# 11_Speak.net
KiCad netlist of a schematic drawn in Altium Designer
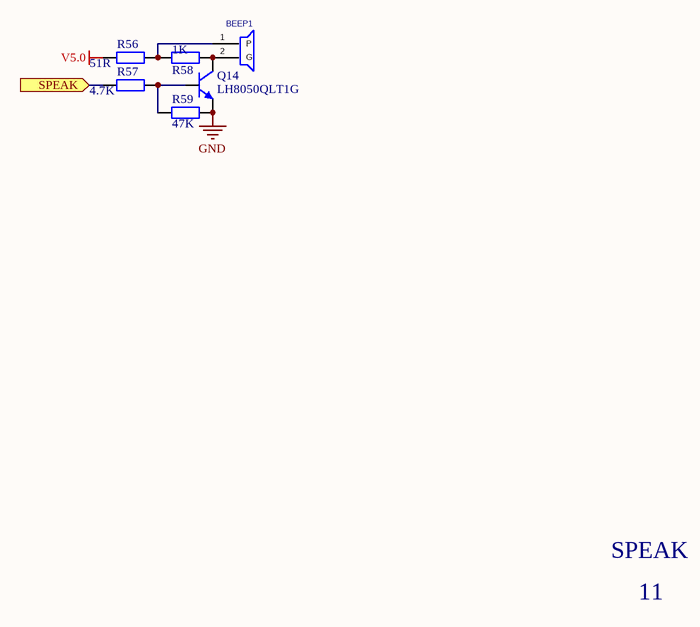
[diagram p0: 11_Speak.SchDoc]

(export (version "E")
  (design (tool "Eeschema 10.0.6"))
  (components
    (comp (ref "BEEP1")
      (value "BEEP-9.5X5.5")
      (footprint "BEEP-9.5X5.5")
      (libsource (lib "MINI-V3") (part "BEEP-9.5X5.5"))
    )
    (comp (ref "Q14")
      (value "LH8050QLT1G")
      (footprint "SOT-23")
      (description "NPN")
      (libsource (lib "XiaoyI") (part "NPN-1"))
    )
    (comp (ref "R56")
      (value "51R")
      (footprint "SMD-0603")
      (description "贴片电阻 5%")
      (libsource (lib "") (part "RES0_1"))
    )
    (comp (ref "R57")
      (value "4.7K")
      (footprint "SMD-0603")
      (description "贴片电阻 5%")
      (libsource (lib "ABB") (part "RES0"))
    )
    (comp (ref "R58")
      (value "1K")
      (footprint "SMD-0603")
      (description "贴片电阻 5%")
      (libsource (lib "") (part "RES0_1"))
    )
    (comp (ref "R59")
      (value "47K")
      (footprint "SMD-0603")
      (description "贴片电阻 5%")
      (libsource (lib "ABB") (part "RES0"))
    )
  )
  (nets
    (net (code "1") (name "/SPEAK") (class "Default")
      (node (ref "R57") (pin "1") (pinfunction "1_1") (pintype "passive"))
    )
    (net (code "2") (name "GND") (class "Default")
      (node (ref "Q14") (pin "2") (pinfunction "E_2") (pintype "passive"))
      (node (ref "R59") (pin "2") (pinfunction "2_2") (pintype "passive"))
    )
    (net (code "3") (name "Net-(BEEP1-G)") (class "Default")
      (node (ref "BEEP1") (pin "2") (pinfunction "G_2") (pintype "passive"))
      (node (ref "Q14") (pin "3") (pinfunction "C_3") (pintype "passive"))
      (node (ref "R58") (pin "1") (pinfunction "1_1") (pintype "passive"))
    )
    (net (code "4") (name "Net-(BEEP1-P)") (class "Default")
      (node (ref "BEEP1") (pin "1") (pinfunction "P_1") (pintype "passive"))
      (node (ref "R56") (pin "1") (pinfunction "1_1") (pintype "passive"))
      (node (ref "R58") (pin "2") (pinfunction "2_2") (pintype "passive"))
    )
    (net (code "5") (name "Net-(Q14-B)") (class "Default")
      (node (ref "Q14") (pin "1") (pinfunction "B_1") (pintype "passive"))
      (node (ref "R57") (pin "2") (pinfunction "2_2") (pintype "passive"))
      (node (ref "R59") (pin "1") (pinfunction "1_1") (pintype "passive"))
    )
    (net (code "6") (name "V5.0") (class "Default")
      (node (ref "R56") (pin "2") (pinfunction "2_2") (pintype "passive"))
    )
  )
)
